# encoderkit.net
KiCad netlist of a schematic drawn in EAGLE
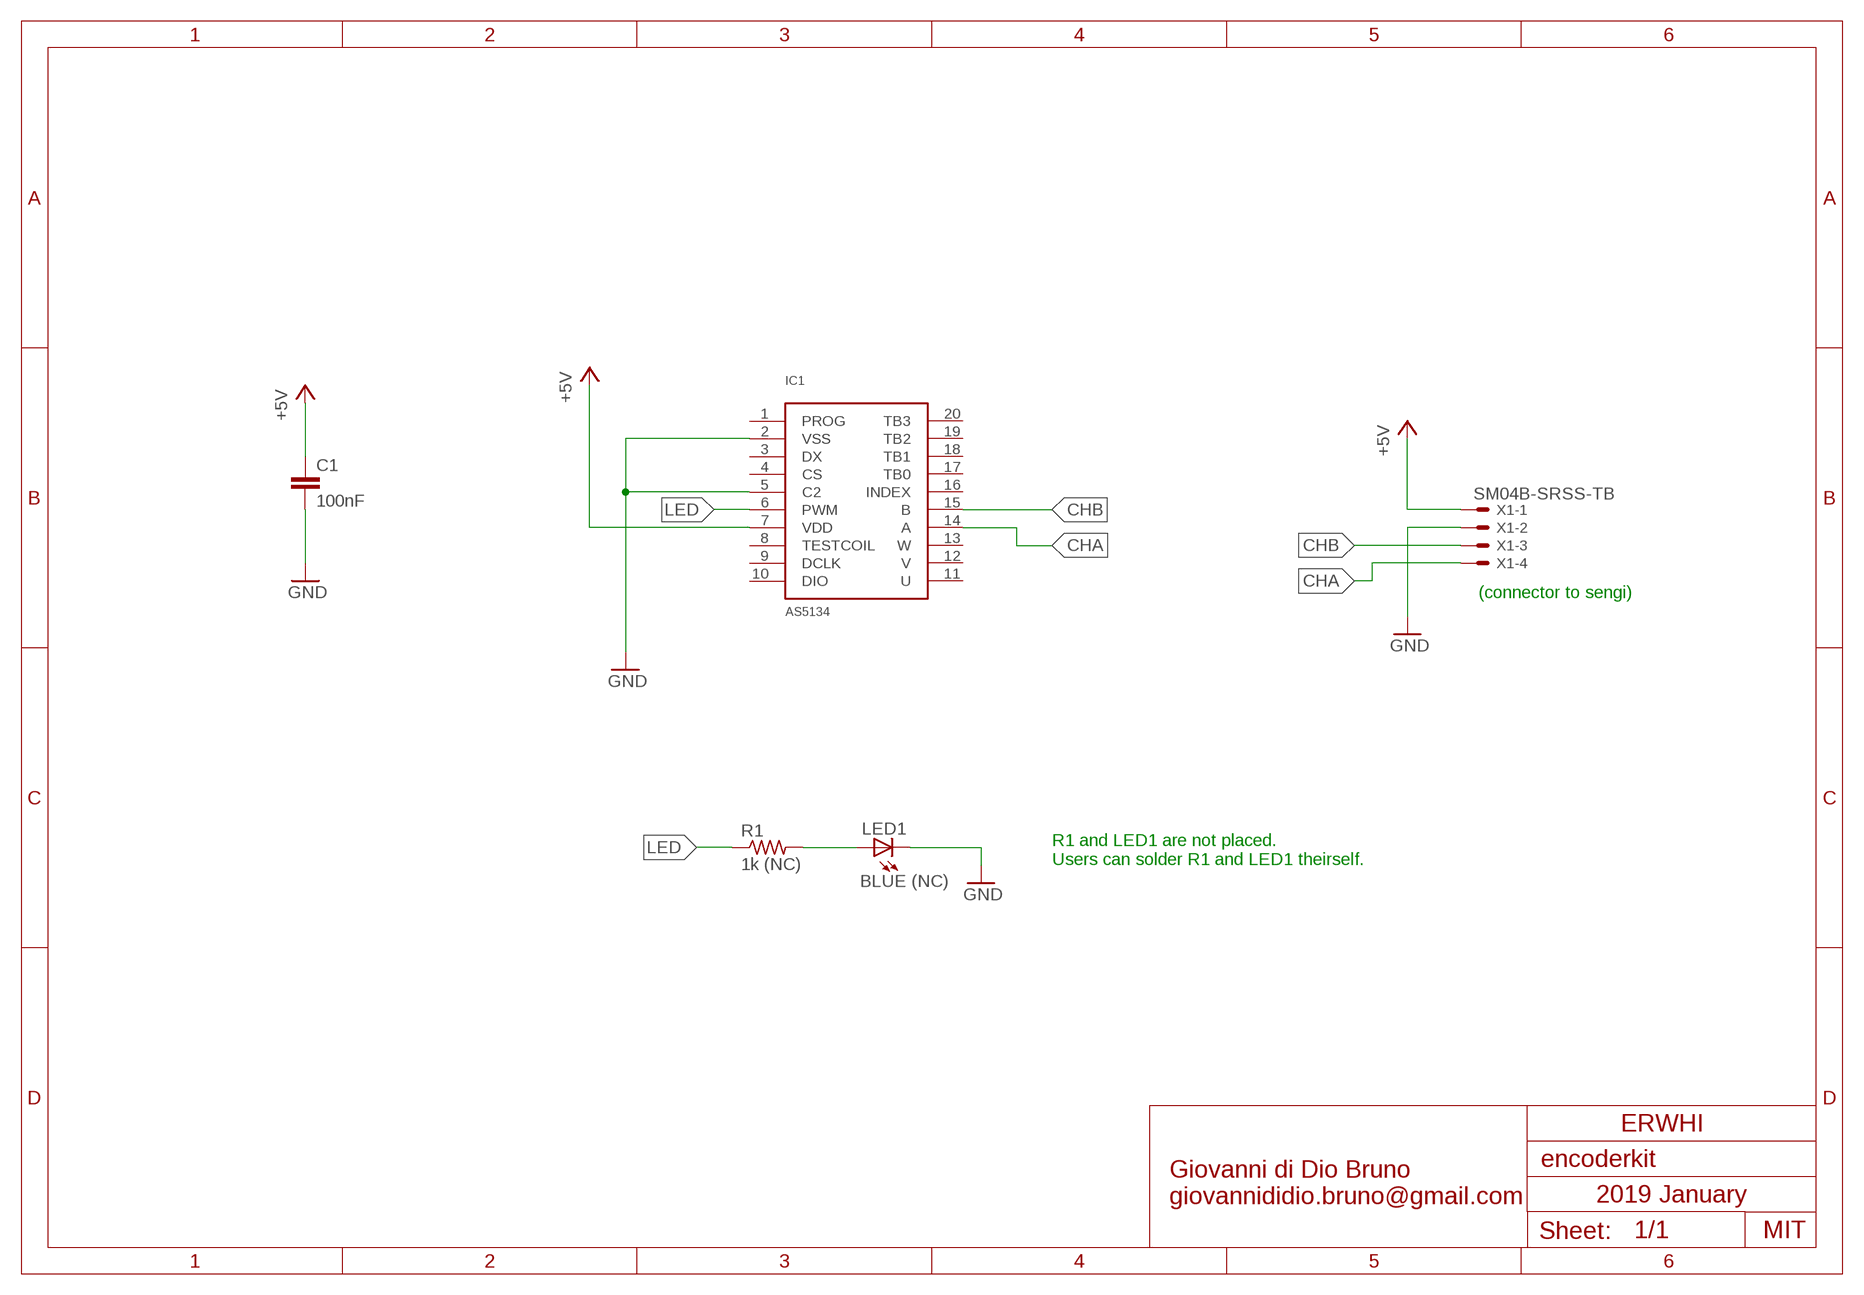
[diagram p0: schematic, sheet 1]

(export (version "E")
  (design (tool "Eeschema 10.0.6"))
  (components
    (comp (ref "C1")
      (value "100nF")
      (footprint "eagle-import:C0402")
      (libsource (lib "eagle-import") (part "C-EUC0402"))
    )
    (comp (ref "IC1")
      (value "AS5134")
      (footprint "eagle-import:SSOP20")
      (libsource (lib "eagle-import") (part "AS5134"))
    )
    (comp (ref "LED1")
      (value "BLUE (NC)")
      (footprint "eagle-import:CHIP-LED0603")
      (libsource (lib "eagle-import") (part "LEDCHIP-LED0603"))
    )
    (comp (ref "R1")
      (value "1k (NC)")
      (footprint "eagle-import:R0402")
      (libsource (lib "eagle-import") (part "R-US_R0402"))
    )
    (comp (ref "X1")
      (value "SM04B-SRSS-TB")
      (footprint "eagle-import:SM04B-SRSS-TB")
      (libsource (lib "eagle-import") (part "?M04B-SRSS-TBS"))
    )
  )
  (nets
    (net (code "1") (name "+5V") (class "Default")
      (node (ref "C1") (pin "1") (pinfunction "1_1") (pintype "passive"))
      (node (ref "IC1") (pin "7") (pinfunction "VDD_7") (pintype "bidirectional"))
      (node (ref "X1") (pin "1") (pinfunction "S_1") (pintype "passive"))
    )
    (net (code "2") (name "CHA") (class "Default")
      (node (ref "IC1") (pin "14") (pinfunction "A_14") (pintype "bidirectional"))
      (node (ref "X1") (pin "4") (pinfunction "S_4") (pintype "passive"))
    )
    (net (code "3") (name "CHB") (class "Default")
      (node (ref "IC1") (pin "15") (pinfunction "B_15") (pintype "bidirectional"))
      (node (ref "X1") (pin "3") (pinfunction "S_3") (pintype "passive"))
    )
    (net (code "4") (name "GND") (class "Default")
      (node (ref "C1") (pin "2") (pinfunction "2_2") (pintype "passive"))
      (node (ref "IC1") (pin "2") (pinfunction "VSS_2") (pintype "bidirectional"))
      (node (ref "IC1") (pin "5") (pinfunction "C2_5") (pintype "bidirectional"))
      (node (ref "LED1") (pin "C") (pinfunction "C_C") (pintype "passive"))
      (node (ref "X1") (pin "2") (pinfunction "S_2") (pintype "passive"))
    )
    (net (code "5") (name "LED") (class "Default")
      (node (ref "IC1") (pin "6") (pinfunction "PWM_6") (pintype "bidirectional"))
      (node (ref "R1") (pin "1") (pinfunction "1_1") (pintype "passive"))
    )
    (net (code "6") (name "Net-(LED1-PadA)") (class "Default")
      (node (ref "LED1") (pin "A") (pinfunction "A_A") (pintype "passive"))
      (node (ref "R1") (pin "2") (pinfunction "2_2") (pintype "passive"))
    )
    (net (code "7") (name "unconnected-(IC1-CS-Pad4)") (class "Default")
      (node (ref "IC1") (pin "4") (pinfunction "CS_4") (pintype "bidirectional"))
    )
    (net (code "8") (name "unconnected-(IC1-DCLK-Pad9)") (class "Default")
      (node (ref "IC1") (pin "9") (pinfunction "DCLK_9") (pintype "bidirectional"))
    )
    (net (code "9") (name "unconnected-(IC1-DIO-Pad10)") (class "Default")
      (node (ref "IC1") (pin "10") (pinfunction "DIO_10") (pintype "bidirectional"))
    )
    (net (code "10") (name "unconnected-(IC1-DX-Pad3)") (class "Default")
      (node (ref "IC1") (pin "3") (pinfunction "DX_3") (pintype "bidirectional"))
    )
    (net (code "11") (name "unconnected-(IC1-INDEX-Pad16)") (class "Default")
      (node (ref "IC1") (pin "16") (pinfunction "INDEX_16") (pintype "bidirectional"))
    )
    (net (code "12") (name "unconnected-(IC1-PROG-Pad1)") (class "Default")
      (node (ref "IC1") (pin "1") (pinfunction "PROG_1") (pintype "bidirectional"))
    )
    (net (code "13") (name "unconnected-(IC1-TB0-Pad17)") (class "Default")
      (node (ref "IC1") (pin "17") (pinfunction "TB0_17") (pintype "bidirectional"))
    )
    (net (code "14") (name "unconnected-(IC1-TB1-Pad18)") (class "Default")
      (node (ref "IC1") (pin "18") (pinfunction "TB1_18") (pintype "bidirectional"))
    )
    (net (code "15") (name "unconnected-(IC1-TB2-Pad19)") (class "Default")
      (node (ref "IC1") (pin "19") (pinfunction "TB2_19") (pintype "bidirectional"))
    )
    (net (code "16") (name "unconnected-(IC1-TB3-Pad20)") (class "Default")
      (node (ref "IC1") (pin "20") (pinfunction "TB3_20") (pintype "bidirectional"))
    )
    (net (code "17") (name "unconnected-(IC1-TESTCOIL-Pad8)") (class "Default")
      (node (ref "IC1") (pin "8") (pinfunction "TESTCOIL_8") (pintype "bidirectional"))
    )
    (net (code "18") (name "unconnected-(IC1-U-Pad11)") (class "Default")
      (node (ref "IC1") (pin "11") (pinfunction "U_11") (pintype "bidirectional"))
    )
    (net (code "19") (name "unconnected-(IC1-V-Pad12)") (class "Default")
      (node (ref "IC1") (pin "12") (pinfunction "V_12") (pintype "bidirectional"))
    )
    (net (code "20") (name "unconnected-(IC1-W-Pad13)") (class "Default")
      (node (ref "IC1") (pin "13") (pinfunction "W_13") (pintype "bidirectional"))
    )
  )
)
